# Usb_to_Uart.net
KiCad netlist of a schematic drawn in Altium Designer
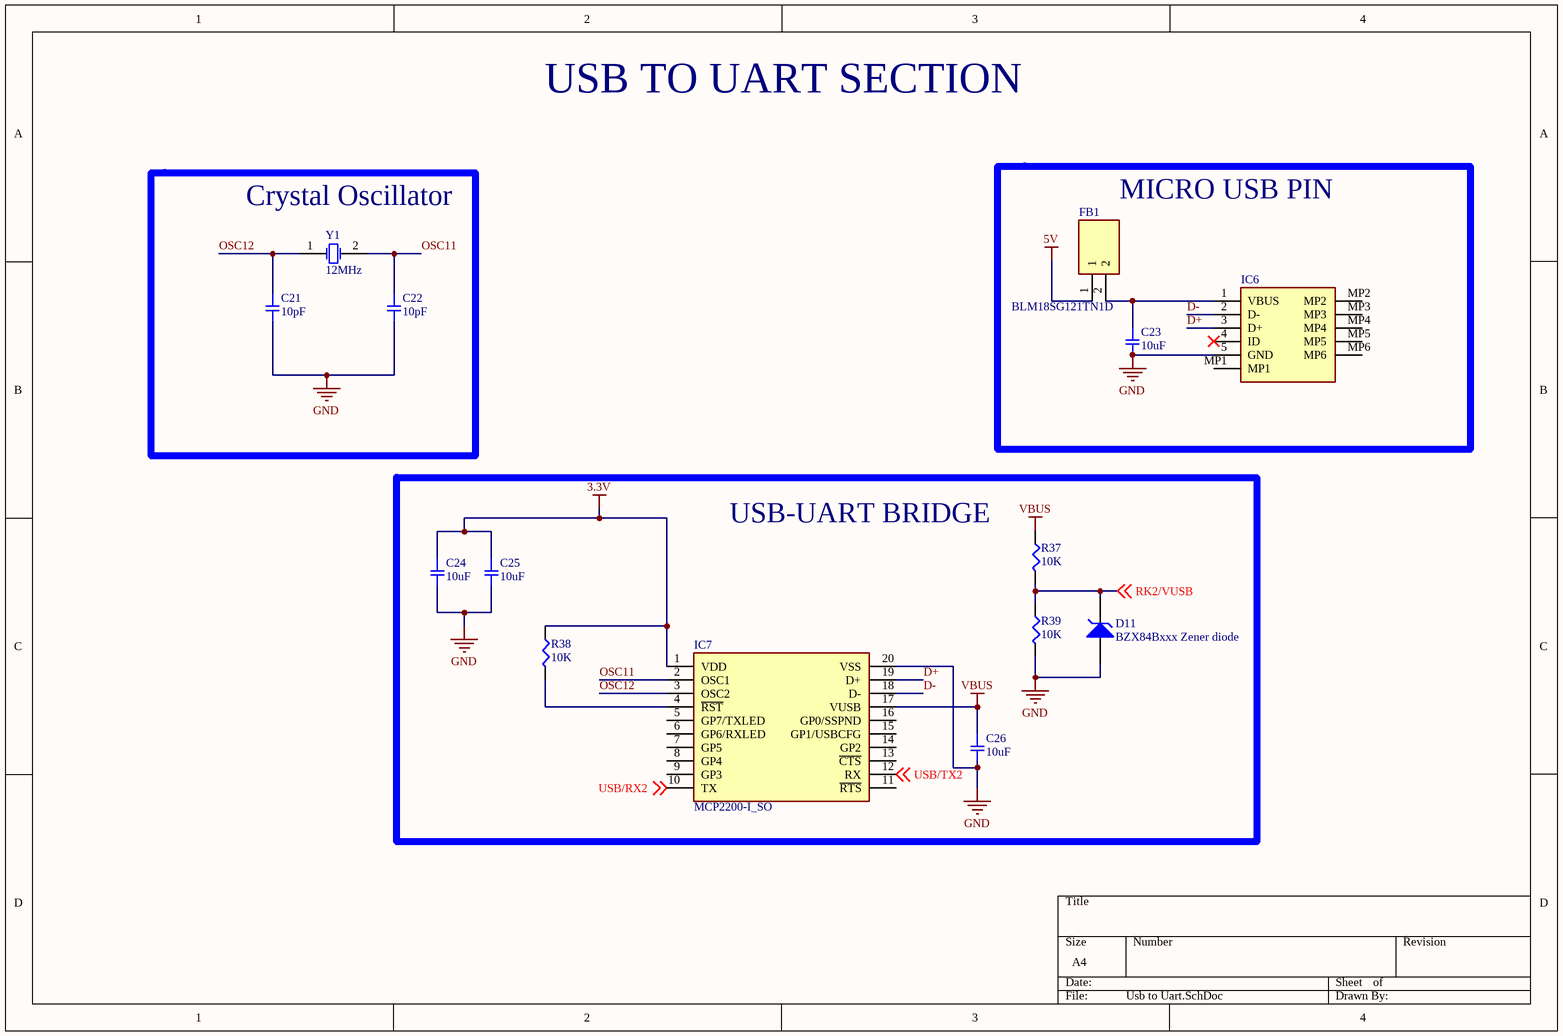
[diagram p0: Usb to Uart.SchDoc]

(export (version "E")
  (design (tool "Eeschema 10.0.6"))
  (components
    (comp (ref "C21")
      (value "10pF")
      (footprint "SMD-0805C")
      (description "CAP CER 0.1UF 50V X7R 0805")
      (fields
        (field (name "DIGI-KEY PART NUMBER") "490-11955-1-ND")
        (field (name "PART NUMBER") "GCD21BR71H104KA01L")
      )
      (libsource (lib "capacitor_murata_0805") (part "GCD21BR71H104KA01L"))
    )
    (comp (ref "C22")
      (value "10pF")
      (footprint "SMD-0805C")
      (description "CAP CER 0.1UF 50V X7R 0805")
      (fields
        (field (name "DIGI-KEY PART NUMBER") "490-11955-1-ND")
        (field (name "PART NUMBER") "GCD21BR71H104KA01L")
      )
      (libsource (lib "capacitor_murata_0805") (part "GCD21BR71H104KA01L"))
    )
    (comp (ref "C23")
      (value "10uF")
      (footprint "SMD-0805C")
      (description "CAP CER 0.1UF 50V X7R 0805")
      (fields
        (field (name "DIGI-KEY PART NUMBER") "490-11955-1-ND")
        (field (name "PART NUMBER") "GCD21BR71H104KA01L")
      )
      (libsource (lib "capacitor_murata_0805") (part "GCD21BR71H104KA01L"))
    )
    (comp (ref "C24")
      (value "10uF")
      (footprint "SMD-0805C")
      (description "CAP CER 0.1UF 50V X7R 0805")
      (fields
        (field (name "DIGI-KEY PART NUMBER") "490-11955-1-ND")
        (field (name "PART NUMBER") "GCD21BR71H104KA01L")
      )
      (libsource (lib "capacitor_murata_0805") (part "GCD21BR71H104KA01L"))
    )
    (comp (ref "C25")
      (value "10uF")
      (footprint "SMD-0805C")
      (description "CAP CER 0.1UF 50V X7R 0805")
      (fields
        (field (name "DIGI-KEY PART NUMBER") "490-11955-1-ND")
        (field (name "PART NUMBER") "GCD21BR71H104KA01L")
      )
      (libsource (lib "capacitor_murata_0805") (part "GCD21BR71H104KA01L"))
    )
    (comp (ref "C26")
      (value "10uF")
      (footprint "SMD-0805C")
      (description "CAP CER 0.1UF 50V X7R 0805")
      (fields
        (field (name "DIGI-KEY PART NUMBER") "490-11955-1-ND")
        (field (name "PART NUMBER") "GCD21BR71H104KA01L")
      )
      (libsource (lib "capacitor_murata_0805") (part "GCD21BR71H104KA01L"))
    )
    (comp (ref "D11")
      (value "BZX84Bxxx Zener diode")
      (footprint "SOT95P240X120-3N")
      (description "BZX84Bxxx SMD Zener Diode SOT-23")
      (libsource (lib "PN Diodes my  Integrated libray") (part "BZX84Bxxx Zener diode"))
    )
    (comp (ref "FB1")
      (value "BLM18SG121TN1D")
      (footprint "SamacSys:BLM18EG101TH1D")
      (description "Ferrite Bead")
      (fields (field (name "MOUSER PART NUMBER") "81-BLM18SG121TN1D"))
      (libsource (lib "*") (part "BLM18SG121TN1D"))
    )
    (comp (ref "IC6")
      (value "~")
      (footprint "SamacSys:0473461001")
      (description "Connector")
      (fields (field (name "MANUFACTURER_PART_NUMBER") "0473461001"))
      (libsource (lib "*") (part "0473461001"))
    )
    (comp (ref "IC7")
      (value "MCP2200-I_SO")
      (footprint "SamacSys:SOIC127P1030X265-20N")
      (description "Integrated Circuit")
      (fields
        (field (name "MANUFACTURER_PART_NUMBER") "MCP2200-I/SO")
        (field (name "MOUSER PART NUMBER") "579-MCP2200-I/SO")
      )
      (libsource (lib "*") (part "MCP2200-I_SO"))
    )
    (comp (ref "R37")
      (value "10K")
      (footprint "SMD-0805-RES")
      (description "RES SMD 1K OHM 1% 1/8W 0805")
      (fields
        (field (name "PART NUMBER") "ERJ-6ENF1001V")
        (field (name "DIGI-KEY PART NUMBER") "P1.00KCCT-ND")
      )
      (libsource (lib "Panasonic_ERJ_0805") (part "ERJ-6ENF1001V"))
    )
    (comp (ref "R38")
      (value "10K")
      (footprint "SMD-0805-RES")
      (description "RES SMD 1K OHM 1% 1/8W 0805")
      (fields
        (field (name "PART NUMBER") "ERJ-6ENF1001V")
        (field (name "DIGI-KEY PART NUMBER") "P1.00KCCT-ND")
      )
      (libsource (lib "Panasonic_ERJ_0805") (part "ERJ-6ENF1001V"))
    )
    (comp (ref "R39")
      (value "10K")
      (footprint "SMD-0805-RES")
      (description "RES SMD 1K OHM 1% 1/8W 0805")
      (fields
        (field (name "PART NUMBER") "ERJ-6ENF1001V")
        (field (name "DIGI-KEY PART NUMBER") "P1.00KCCT-ND")
      )
      (libsource (lib "Panasonic_ERJ_0805") (part "ERJ-6ENF1001V"))
    )
    (comp (ref "Y1")
      (value "12MHz")
      (footprint "Mini Crystal")
      (description "9B-64.000MBBK-B")
      (fields (field (name "MANUFACTURER") "Abracon") (field (name "PARTNUMBER") "ABLS2-4.096MHZ-D4Y-T"))
      (libsource (lib "Medi Custom library") (part "Mini Crystal"))
    )
  )
  (nets
    (net (code "1") (name "/D+") (class "Default")
      (node (ref "IC6") (pin "3") (pinfunction "D+_3") (pintype "passive"))
      (node (ref "IC7") (pin "19") (pinfunction "D+_19") (pintype "passive"))
    )
    (net (code "2") (name "/D-") (class "Default")
      (node (ref "IC6") (pin "2") (pinfunction "D-_2") (pintype "passive"))
      (node (ref "IC7") (pin "18") (pinfunction "D-_18") (pintype "passive"))
    )
    (net (code "3") (name "/OSC11") (class "Default")
      (node (ref "C22") (pin "1") (pinfunction "1_1") (pintype "passive"))
      (node (ref "IC7") (pin "2") (pinfunction "OSC1_2") (pintype "passive"))
      (node (ref "Y1") (pin "2") (pinfunction "X2_2") (pintype "passive"))
    )
    (net (code "4") (name "/OSC12") (class "Default")
      (node (ref "C21") (pin "1") (pinfunction "1_1") (pintype "passive"))
      (node (ref "IC7") (pin "3") (pinfunction "OSC2_3") (pintype "passive"))
      (node (ref "Y1") (pin "1") (pinfunction "X1_1") (pintype "passive"))
    )
    (net (code "5") (name "3.3V") (class "Default")
      (node (ref "C24") (pin "1") (pinfunction "1_1") (pintype "passive"))
      (node (ref "C25") (pin "1") (pinfunction "1_1") (pintype "passive"))
      (node (ref "IC7") (pin "1") (pinfunction "VDD_1") (pintype "passive"))
      (node (ref "R38") (pin "1") (pinfunction "1_1") (pintype "passive"))
    )
    (net (code "6") (name "5V") (class "Default")
      (node (ref "FB1") (pin "1") (pinfunction "1_1") (pintype "passive"))
    )
    (net (code "7") (name "GND") (class "Default")
      (node (ref "C21") (pin "2") (pinfunction "2_2") (pintype "passive"))
      (node (ref "C22") (pin "2") (pinfunction "2_2") (pintype "passive"))
      (node (ref "C23") (pin "2") (pinfunction "2_2") (pintype "passive"))
      (node (ref "C24") (pin "2") (pinfunction "2_2") (pintype "passive"))
      (node (ref "C25") (pin "2") (pinfunction "2_2") (pintype "passive"))
      (node (ref "C26") (pin "2") (pinfunction "2_2") (pintype "passive"))
      (node (ref "D11") (pin "1") (pinfunction "A_1") (pintype "passive"))
      (node (ref "IC6") (pin "5") (pinfunction "GND_5") (pintype "passive"))
      (node (ref "IC7") (pin "20") (pinfunction "VSS_20") (pintype "passive"))
      (node (ref "R39") (pin "2") (pinfunction "2_2") (pintype "passive"))
    )
    (net (code "8") (name "Net-(IC6-VBUS)") (class "Default")
      (node (ref "C23") (pin "1") (pinfunction "1_1") (pintype "passive"))
      (node (ref "FB1") (pin "2") (pinfunction "2_2") (pintype "passive"))
      (node (ref "IC6") (pin "1") (pinfunction "VBUS_1") (pintype "passive"))
    )
    (net (code "9") (name "Net-(IC7-~{RST})") (class "Default")
      (node (ref "IC7") (pin "4") (pinfunction "~{RST}_4") (pintype "passive"))
      (node (ref "R38") (pin "2") (pinfunction "2_2") (pintype "passive"))
    )
    (net (code "10") (name "RK2{slash}VUSB") (class "Default")
      (node (ref "D11") (pin "3") (pinfunction "K_3") (pintype "passive"))
      (node (ref "R37") (pin "2") (pinfunction "2_2") (pintype "passive"))
      (node (ref "R39") (pin "1") (pinfunction "1_1") (pintype "passive"))
    )
    (net (code "11") (name "USB{slash}RX2") (class "Default")
      (node (ref "IC7") (pin "10") (pinfunction "TX_10") (pintype "passive"))
    )
    (net (code "12") (name "USB{slash}TX2") (class "Default")
      (node (ref "IC7") (pin "12") (pinfunction "RX_12") (pintype "passive"))
    )
    (net (code "13") (name "VBUS") (class "Default")
      (node (ref "C26") (pin "1") (pinfunction "1_1") (pintype "passive"))
      (node (ref "IC7") (pin "17") (pinfunction "VUSB_17") (pintype "passive"))
      (node (ref "R37") (pin "1") (pinfunction "1_1") (pintype "passive"))
    )
    (net (code "14") (name "unconnected-(IC6-ID-Pad4)") (class "Default")
      (node (ref "IC6") (pin "4") (pinfunction "ID_4") (pintype "passive+no_connect"))
    )
    (net (code "15") (name "unconnected-(IC6-PadMP1)") (class "Default")
      (node (ref "IC6") (pin "MP1") (pinfunction "MP1_MP1") (pintype "passive"))
    )
    (net (code "16") (name "unconnected-(IC6-PadMP2)") (class "Default")
      (node (ref "IC6") (pin "MP2") (pinfunction "MP2_MP2") (pintype "passive"))
    )
    (net (code "17") (name "unconnected-(IC6-PadMP3)") (class "Default")
      (node (ref "IC6") (pin "MP3") (pinfunction "MP3_MP3") (pintype "passive"))
    )
    (net (code "18") (name "unconnected-(IC6-PadMP4)") (class "Default")
      (node (ref "IC6") (pin "MP4") (pinfunction "MP4_MP4") (pintype "passive"))
    )
    (net (code "19") (name "unconnected-(IC6-PadMP5)") (class "Default")
      (node (ref "IC6") (pin "MP5") (pinfunction "MP5_MP5") (pintype "passive"))
    )
    (net (code "20") (name "unconnected-(IC6-PadMP6)") (class "Default")
      (node (ref "IC6") (pin "MP6") (pinfunction "MP6_MP6") (pintype "passive"))
    )
    (net (code "21") (name "unconnected-(IC7-GP0{slash}SSPND-Pad16)") (class "Default")
      (node (ref "IC7") (pin "16") (pinfunction "GP0/SSPND_16") (pintype "passive"))
    )
    (net (code "22") (name "unconnected-(IC7-GP1{slash}USBCFG-Pad15)") (class "Default")
      (node (ref "IC7") (pin "15") (pinfunction "GP1/USBCFG_15") (pintype "passive"))
    )
    (net (code "23") (name "unconnected-(IC7-GP2-Pad14)") (class "Default")
      (node (ref "IC7") (pin "14") (pinfunction "GP2_14") (pintype "passive"))
    )
    (net (code "24") (name "unconnected-(IC7-GP3-Pad9)") (class "Default")
      (node (ref "IC7") (pin "9") (pinfunction "GP3_9") (pintype "passive"))
    )
    (net (code "25") (name "unconnected-(IC7-GP4-Pad8)") (class "Default")
      (node (ref "IC7") (pin "8") (pinfunction "GP4_8") (pintype "passive"))
    )
    (net (code "26") (name "unconnected-(IC7-GP5-Pad7)") (class "Default")
      (node (ref "IC7") (pin "7") (pinfunction "GP5_7") (pintype "passive"))
    )
    (net (code "27") (name "unconnected-(IC7-GP6{slash}RXLED-Pad6)") (class "Default")
      (node (ref "IC7") (pin "6") (pinfunction "GP6/RXLED_6") (pintype "passive"))
    )
    (net (code "28") (name "unconnected-(IC7-GP7{slash}TXLED-Pad5)") (class "Default")
      (node (ref "IC7") (pin "5") (pinfunction "GP7/TXLED_5") (pintype "passive"))
    )
    (net (code "29") (name "unconnected-(IC7-~{CTS}-Pad13)") (class "Default")
      (node (ref "IC7") (pin "13") (pinfunction "~{CTS}_13") (pintype "passive"))
    )
    (net (code "30") (name "unconnected-(IC7-~{RTS}-Pad11)") (class "Default")
      (node (ref "IC7") (pin "11") (pinfunction "~{RTS}_11") (pintype "passive"))
    )
  )
)
